# 74HC165_SMD.net
KiCad netlist of a schematic drawn in Altium Designer
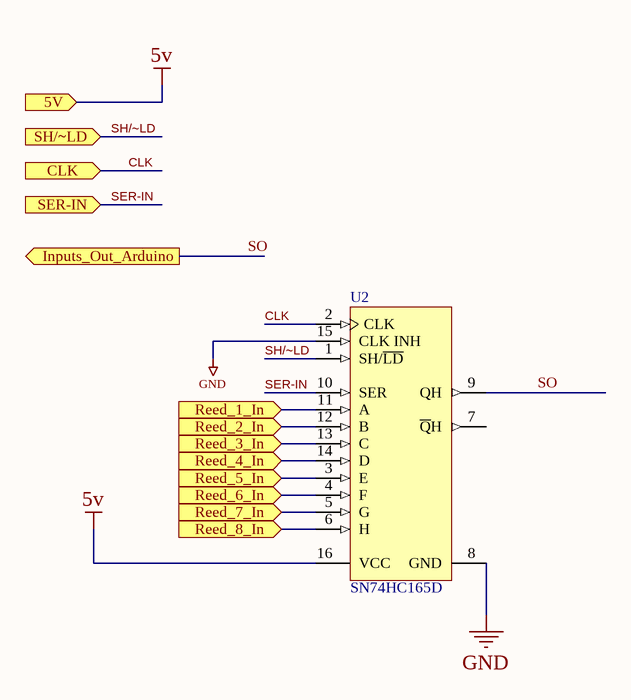
[diagram p0: 74HC165_SMD.SchDoc]

(export (version "E")
  (design (tool "Eeschema 10.0.6"))
  (components
    (comp (ref "U2")
      (value "SN74HC165D")
      (footprint "D0016A_L")
      (description "8-Bit Parallel-Load Shift Registers, D0016A, TUBE")
      (fields
        (field (name "MANUFACTURER") "Texas Instruments")
        (field (name "GENERIC PART NUMBER") "SN74HC165")
      )
      (libsource (lib "Altium Content Vault") (part "TI-SNX4XXX165X-16"))
    )
  )
  (nets
    (net (code "1") (name "/CLK") (class "Default")
      (node (ref "U2") (pin "2") (pinfunction "CLK_2") (pintype "input"))
    )
    (net (code "2") (name "/Reed_1_In") (class "Default")
      (node (ref "U2") (pin "11") (pinfunction "A_11") (pintype "input"))
    )
    (net (code "3") (name "/Reed_2_In") (class "Default")
      (node (ref "U2") (pin "12") (pinfunction "B_12") (pintype "input"))
    )
    (net (code "4") (name "/Reed_3_In") (class "Default")
      (node (ref "U2") (pin "13") (pinfunction "C_13") (pintype "input"))
    )
    (net (code "5") (name "/Reed_4_In") (class "Default")
      (node (ref "U2") (pin "14") (pinfunction "D_14") (pintype "input"))
    )
    (net (code "6") (name "/Reed_5_In") (class "Default")
      (node (ref "U2") (pin "3") (pinfunction "E_3") (pintype "input"))
    )
    (net (code "7") (name "/Reed_6_In") (class "Default")
      (node (ref "U2") (pin "4") (pinfunction "F_4") (pintype "input"))
    )
    (net (code "8") (name "/Reed_7_In") (class "Default")
      (node (ref "U2") (pin "5") (pinfunction "G_5") (pintype "input"))
    )
    (net (code "9") (name "/Reed_8_In") (class "Default")
      (node (ref "U2") (pin "6") (pinfunction "H_6") (pintype "input"))
    )
    (net (code "10") (name "/SER-IN") (class "Default")
      (node (ref "U2") (pin "10") (pinfunction "SER_10") (pintype "input"))
    )
    (net (code "11") (name "/SH{slash}~LD") (class "Default")
      (node (ref "U2") (pin "1") (pinfunction "SH/~{LD}_1") (pintype "input"))
    )
    (net (code "12") (name "/SO") (class "Default")
      (node (ref "U2") (pin "9") (pinfunction "QH_9") (pintype "output"))
    )
    (net (code "13") (name "5v") (class "Default")
      (node (ref "U2") (pin "16") (pinfunction "VCC_16") (pintype "power_in"))
    )
    (net (code "14") (name "GND") (class "Default")
      (node (ref "U2") (pin "15") (pinfunction "CLK_INH_15") (pintype "input"))
      (node (ref "U2") (pin "8") (pinfunction "GND_8") (pintype "power_in"))
    )
    (net (code "15") (name "unconnected-(U2-~{Q}H-Pad7)") (class "Default")
      (node (ref "U2") (pin "7") (pinfunction "~{Q}H_7") (pintype "output"))
    )
  )
)
